# PCB-ENCODER2a.net
KiCad netlist of a schematic drawn in EAGLE
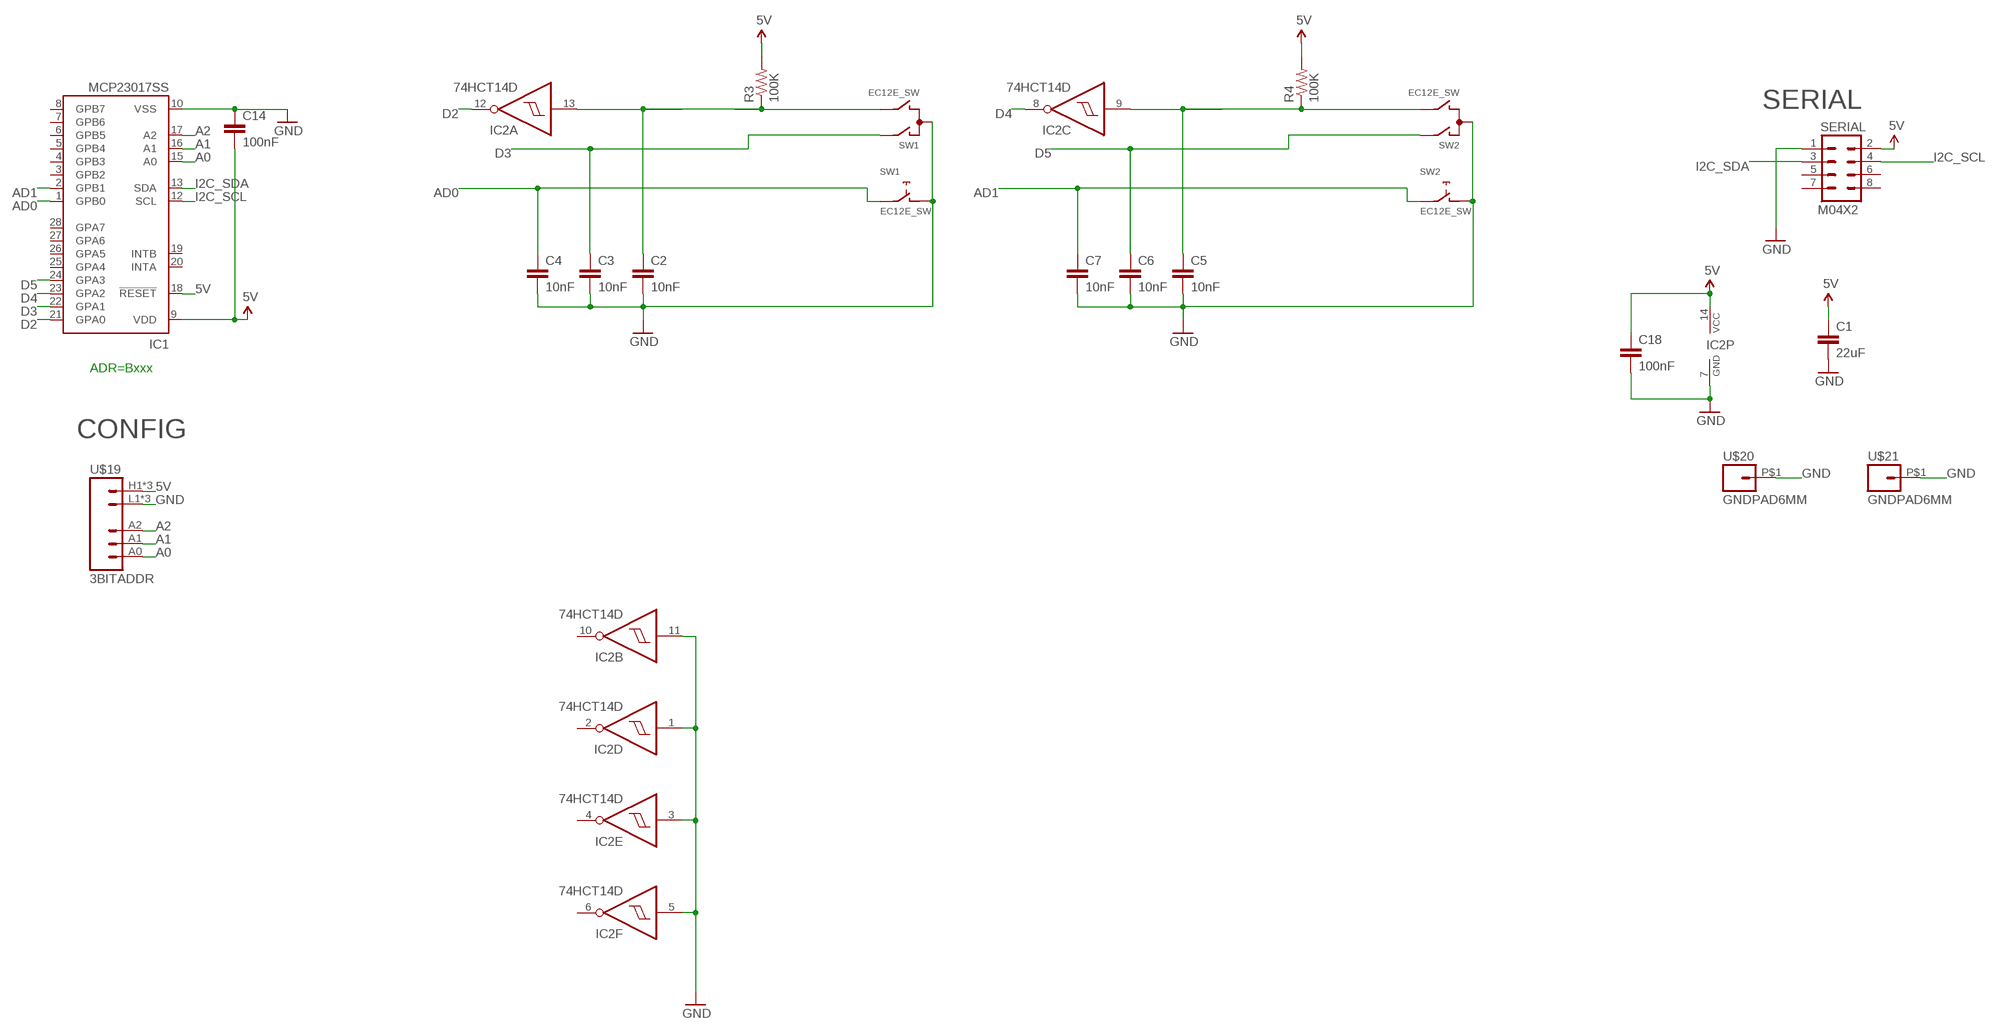
[diagram p0: schematic, sheet 1]

(export (version "E")
  (design (tool "Eeschema 10.0.6"))
  (components
    (comp (ref "C1")
      (value "22uF")
      (footprint "eagle-import:0805")
      (libsource (lib "eagle-import") (part "CAP0805"))
    )
    (comp (ref "C2")
      (value "10nF")
      (footprint "eagle-import:0603-CAP")
      (libsource (lib "eagle-import") (part "CAP0603-CAP"))
    )
    (comp (ref "C3")
      (value "10nF")
      (footprint "eagle-import:0603-CAP")
      (libsource (lib "eagle-import") (part "CAP0603-CAP"))
    )
    (comp (ref "C4")
      (value "10nF")
      (footprint "eagle-import:0603-CAP")
      (libsource (lib "eagle-import") (part "CAP0603-CAP"))
    )
    (comp (ref "C5")
      (value "10nF")
      (footprint "eagle-import:0603-CAP")
      (libsource (lib "eagle-import") (part "CAP0603-CAP"))
    )
    (comp (ref "C6")
      (value "10nF")
      (footprint "eagle-import:0603-CAP")
      (libsource (lib "eagle-import") (part "CAP0603-CAP"))
    )
    (comp (ref "C7")
      (value "10nF")
      (footprint "eagle-import:0603-CAP")
      (libsource (lib "eagle-import") (part "CAP0603-CAP"))
    )
    (comp (ref "C14")
      (value "100nF")
      (footprint "eagle-import:0603-CAP")
      (libsource (lib "eagle-import") (part "CAP0603-CAP"))
    )
    (comp (ref "C18")
      (value "100nF")
      (footprint "eagle-import:0603-CAP")
      (libsource (lib "eagle-import") (part "CAP0603-CAP"))
    )
    (comp (ref "IC1")
      (value "MCP23017SS")
      (footprint "eagle-import:SSOP28")
      (fields
        (field (name "MF") "MICROCHIP")
        (field (name "MPN") "MCP23017-E/SS")
        (field (name "MPN_1") "MCP23017-E/SS")
        (field (name "OC_FARNELL") "1467674")
        (field (name "OC_NEWARK") "31K2960")
      )
      (libsource (lib "eagle-import") (part "MCP23017SS"))
    )
    (comp (ref "IC2")
      (value "74HCT14D")
      (footprint "eagle-import:SO14")
      (libsource (lib "eagle-import") (part "7414DHCT"))
    )
    (comp (ref "R3")
      (value "100K")
      (footprint "eagle-import:0603-RES")
      (libsource (lib "eagle-import") (part "RESISTOR0603-RES"))
    )
    (comp (ref "R4")
      (value "100K")
      (footprint "eagle-import:0603-RES")
      (libsource (lib "eagle-import") (part "RESISTOR0603-RES"))
    )
    (comp (ref "SERIAL")
      (value "M04X2")
      (footprint "eagle-import:2X4")
      (libsource (lib "eagle-import") (part "M04X2"))
    )
    (comp (ref "SW1")
      (value "EC12E_SW")
      (footprint "eagle-import:ALPS_EC12E_SW")
      (fields (field (name "MPN") "EC12E2424407"))
      (libsource (lib "eagle-import") (part "EC12E_SW"))
    )
    (comp (ref "SW2")
      (value "EC12E_SW")
      (footprint "eagle-import:ALPS_EC12E_SW")
      (fields (field (name "MPN") "EC12E2424407"))
      (libsource (lib "eagle-import") (part "EC12E_SW"))
    )
    (comp (ref "U$19")
      (value "3BITADDR")
      (footprint "eagle-import:3BITADDR")
      (libsource (lib "eagle-import") (part "3BITADDR"))
    )
    (comp (ref "U$20")
      (value "GNDPAD6MM")
      (footprint "eagle-import:3.2MMPAD6MM")
      (libsource (lib "eagle-import") (part "GNDPAD6MM"))
    )
    (comp (ref "U$21")
      (value "GNDPAD6MM")
      (footprint "eagle-import:3.2MMPAD6MM")
      (libsource (lib "eagle-import") (part "GNDPAD6MM"))
    )
  )
  (nets
    (net (code "1") (name "/A0") (class "Default")
      (node (ref "IC1") (pin "15") (pinfunction "A0_15") (pintype "input"))
      (node (ref "U$19") (pin "A0") (pinfunction "A0_A0") (pintype "passive"))
    )
    (net (code "2") (name "/A1") (class "Default")
      (node (ref "IC1") (pin "16") (pinfunction "A1_16") (pintype "input"))
      (node (ref "U$19") (pin "A1") (pinfunction "A1_A1") (pintype "passive"))
    )
    (net (code "3") (name "/A2") (class "Default")
      (node (ref "IC1") (pin "17") (pinfunction "A2_17") (pintype "input"))
      (node (ref "U$19") (pin "A2") (pinfunction "A2_A2") (pintype "passive"))
    )
    (net (code "4") (name "/AD0") (class "Default")
      (node (ref "C4") (pin "1") (pinfunction "1_1") (pintype "passive"))
      (node (ref "IC1") (pin "1") (pinfunction "GPB0_1") (pintype "bidirectional"))
      (node (ref "SW1") (pin "E") (pinfunction "2_E") (pintype "passive"))
    )
    (net (code "5") (name "/AD1") (class "Default")
      (node (ref "C7") (pin "1") (pinfunction "1_1") (pintype "passive"))
      (node (ref "IC1") (pin "2") (pinfunction "GPB1_2") (pintype "bidirectional"))
      (node (ref "SW2") (pin "E") (pinfunction "2_E") (pintype "passive"))
    )
    (net (code "6") (name "/D2") (class "Default")
      (node (ref "IC1") (pin "21") (pinfunction "GPA0_21") (pintype "bidirectional"))
      (node (ref "IC2") (pin "12") (pinfunction "O_12") (pintype "output"))
    )
    (net (code "7") (name "/D3") (class "Default")
      (node (ref "C3") (pin "1") (pinfunction "1_1") (pintype "passive"))
      (node (ref "IC1") (pin "22") (pinfunction "GPA1_22") (pintype "bidirectional"))
      (node (ref "SW1") (pin "A") (pinfunction "A_A") (pintype "passive"))
    )
    (net (code "8") (name "/D4") (class "Default")
      (node (ref "IC1") (pin "23") (pinfunction "GPA2_23") (pintype "bidirectional"))
      (node (ref "IC2") (pin "8") (pinfunction "O_8") (pintype "output"))
    )
    (net (code "9") (name "/D5") (class "Default")
      (node (ref "C6") (pin "1") (pinfunction "1_1") (pintype "passive"))
      (node (ref "IC1") (pin "24") (pinfunction "GPA3_24") (pintype "bidirectional"))
      (node (ref "SW2") (pin "A") (pinfunction "A_A") (pintype "passive"))
    )
    (net (code "10") (name "/I2C_SCL") (class "Default")
      (node (ref "IC1") (pin "12") (pinfunction "SCL_12") (pintype "input"))
      (node (ref "SERIAL") (pin "4") (pinfunction "4_4") (pintype "passive"))
    )
    (net (code "11") (name "/I2C_SDA") (class "Default")
      (node (ref "IC1") (pin "13") (pinfunction "SDA_13") (pintype "bidirectional"))
      (node (ref "SERIAL") (pin "3") (pinfunction "3_3") (pintype "passive"))
    )
    (net (code "12") (name "5V") (class "Default")
      (node (ref "C1") (pin "1") (pinfunction "1_1") (pintype "passive"))
      (node (ref "C14") (pin "2") (pinfunction "2_2") (pintype "passive"))
      (node (ref "C18") (pin "1") (pinfunction "1_1") (pintype "passive"))
      (node (ref "IC1") (pin "18") (pinfunction "~{RESET}_18") (pintype "input"))
      (node (ref "IC1") (pin "9") (pinfunction "VDD_9") (pintype "power_in"))
      (node (ref "IC2") (pin "14") (pinfunction "VCC_14") (pintype "power_in"))
      (node (ref "R3") (pin "2") (pinfunction "2_2") (pintype "passive"))
      (node (ref "R4") (pin "2") (pinfunction "2_2") (pintype "passive"))
      (node (ref "SERIAL") (pin "2") (pinfunction "2_2") (pintype "passive"))
      (node (ref "U$19") (pin "H1") (pinfunction "VCC_H1") (pintype "passive"))
      (node (ref "U$19") (pin "H2") (pinfunction "VCC_H2") (pintype "passive"))
      (node (ref "U$19") (pin "H3") (pinfunction "VCC_H3") (pintype "passive"))
    )
    (net (code "13") (name "GND") (class "Default")
      (node (ref "C1") (pin "2") (pinfunction "2_2") (pintype "passive"))
      (node (ref "C14") (pin "1") (pinfunction "1_1") (pintype "passive"))
      (node (ref "C18") (pin "2") (pinfunction "2_2") (pintype "passive"))
      (node (ref "C2") (pin "2") (pinfunction "2_2") (pintype "passive"))
      (node (ref "C3") (pin "2") (pinfunction "2_2") (pintype "passive"))
      (node (ref "C4") (pin "2") (pinfunction "2_2") (pintype "passive"))
      (node (ref "C5") (pin "2") (pinfunction "2_2") (pintype "passive"))
      (node (ref "C6") (pin "2") (pinfunction "2_2") (pintype "passive"))
      (node (ref "C7") (pin "2") (pinfunction "2_2") (pintype "passive"))
      (node (ref "IC1") (pin "10") (pinfunction "VSS_10") (pintype "power_in"))
      (node (ref "IC2") (pin "1") (pinfunction "I_1") (pintype "input"))
      (node (ref "IC2") (pin "11") (pinfunction "I_11") (pintype "input"))
      (node (ref "IC2") (pin "3") (pinfunction "I_3") (pintype "input"))
      (node (ref "IC2") (pin "5") (pinfunction "I_5") (pintype "input"))
      (node (ref "IC2") (pin "7") (pinfunction "GND_7") (pintype "power_in"))
      (node (ref "SERIAL") (pin "1") (pinfunction "1_1") (pintype "passive"))
      (node (ref "SW1") (pin "C") (pinfunction "C_C") (pintype "passive"))
      (node (ref "SW1") (pin "D") (pinfunction "1_D") (pintype "passive"))
      (node (ref "SW2") (pin "C") (pinfunction "C_C") (pintype "passive"))
      (node (ref "SW2") (pin "D") (pinfunction "1_D") (pintype "passive"))
      (node (ref "U$19") (pin "L1") (pinfunction "GND_L1") (pintype "passive"))
      (node (ref "U$19") (pin "L2") (pinfunction "GND_L2") (pintype "passive"))
      (node (ref "U$19") (pin "L3") (pinfunction "GND_L3") (pintype "passive"))
      (node (ref "U$20") (pin "P$1") (pinfunction "1_P$1") (pintype "passive"))
      (node (ref "U$21") (pin "P$1") (pinfunction "1_P$1") (pintype "passive"))
    )
    (net (code "14") (name "Net-(IC2A-I)") (class "Default")
      (node (ref "C2") (pin "1") (pinfunction "1_1") (pintype "passive"))
      (node (ref "IC2") (pin "13") (pinfunction "I_13") (pintype "input"))
      (node (ref "R3") (pin "1") (pinfunction "1_1") (pintype "passive"))
      (node (ref "SW1") (pin "B") (pinfunction "B_B") (pintype "passive"))
    )
    (net (code "15") (name "Net-(IC2C-I)") (class "Default")
      (node (ref "C5") (pin "1") (pinfunction "1_1") (pintype "passive"))
      (node (ref "IC2") (pin "9") (pinfunction "I_9") (pintype "input"))
      (node (ref "R4") (pin "1") (pinfunction "1_1") (pintype "passive"))
      (node (ref "SW2") (pin "B") (pinfunction "B_B") (pintype "passive"))
    )
    (net (code "16") (name "unconnected-(IC1-GPA4-Pad25)") (class "Default")
      (node (ref "IC1") (pin "25") (pinfunction "GPA4_25") (pintype "bidirectional"))
    )
    (net (code "17") (name "unconnected-(IC1-GPA5-Pad26)") (class "Default")
      (node (ref "IC1") (pin "26") (pinfunction "GPA5_26") (pintype "bidirectional"))
    )
    (net (code "18") (name "unconnected-(IC1-GPA6-Pad27)") (class "Default")
      (node (ref "IC1") (pin "27") (pinfunction "GPA6_27") (pintype "bidirectional"))
    )
    (net (code "19") (name "unconnected-(IC1-GPA7-Pad28)") (class "Default")
      (node (ref "IC1") (pin "28") (pinfunction "GPA7_28") (pintype "bidirectional"))
    )
    (net (code "20") (name "unconnected-(IC1-GPB2-Pad3)") (class "Default")
      (node (ref "IC1") (pin "3") (pinfunction "GPB2_3") (pintype "bidirectional"))
    )
    (net (code "21") (name "unconnected-(IC1-GPB3-Pad4)") (class "Default")
      (node (ref "IC1") (pin "4") (pinfunction "GPB3_4") (pintype "bidirectional"))
    )
    (net (code "22") (name "unconnected-(IC1-GPB4-Pad5)") (class "Default")
      (node (ref "IC1") (pin "5") (pinfunction "GPB4_5") (pintype "bidirectional"))
    )
    (net (code "23") (name "unconnected-(IC1-GPB5-Pad6)") (class "Default")
      (node (ref "IC1") (pin "6") (pinfunction "GPB5_6") (pintype "bidirectional"))
    )
    (net (code "24") (name "unconnected-(IC1-GPB6-Pad7)") (class "Default")
      (node (ref "IC1") (pin "7") (pinfunction "GPB6_7") (pintype "bidirectional"))
    )
    (net (code "25") (name "unconnected-(IC1-GPB7-Pad8)") (class "Default")
      (node (ref "IC1") (pin "8") (pinfunction "GPB7_8") (pintype "bidirectional"))
    )
    (net (code "26") (name "unconnected-(IC1-INTA-Pad20)") (class "Default")
      (node (ref "IC1") (pin "20") (pinfunction "INTA_20") (pintype "output"))
    )
    (net (code "27") (name "unconnected-(IC1-INTB-Pad19)") (class "Default")
      (node (ref "IC1") (pin "19") (pinfunction "INTB_19") (pintype "output"))
    )
    (net (code "28") (name "unconnected-(IC2B-O-Pad10)") (class "Default")
      (node (ref "IC2") (pin "10") (pinfunction "O_10") (pintype "output"))
    )
    (net (code "29") (name "unconnected-(IC2D-O-Pad2)") (class "Default")
      (node (ref "IC2") (pin "2") (pinfunction "O_2") (pintype "output"))
    )
    (net (code "30") (name "unconnected-(IC2E-O-Pad4)") (class "Default")
      (node (ref "IC2") (pin "4") (pinfunction "O_4") (pintype "output"))
    )
    (net (code "31") (name "unconnected-(IC2F-O-Pad6)") (class "Default")
      (node (ref "IC2") (pin "6") (pinfunction "O_6") (pintype "output"))
    )
    (net (code "32") (name "unconnected-(SERIAL-Pad5)") (class "Default")
      (node (ref "SERIAL") (pin "5") (pinfunction "5_5") (pintype "passive"))
    )
    (net (code "33") (name "unconnected-(SERIAL-Pad6)") (class "Default")
      (node (ref "SERIAL") (pin "6") (pinfunction "6_6") (pintype "passive"))
    )
    (net (code "34") (name "unconnected-(SERIAL-Pad7)") (class "Default")
      (node (ref "SERIAL") (pin "7") (pinfunction "7_7") (pintype "passive"))
    )
    (net (code "35") (name "unconnected-(SERIAL-Pad8)") (class "Default")
      (node (ref "SERIAL") (pin "8") (pinfunction "8_8") (pintype "passive"))
    )
  )
)
